# Task2.net
KiCad netlist of a schematic drawn in Altium Designer
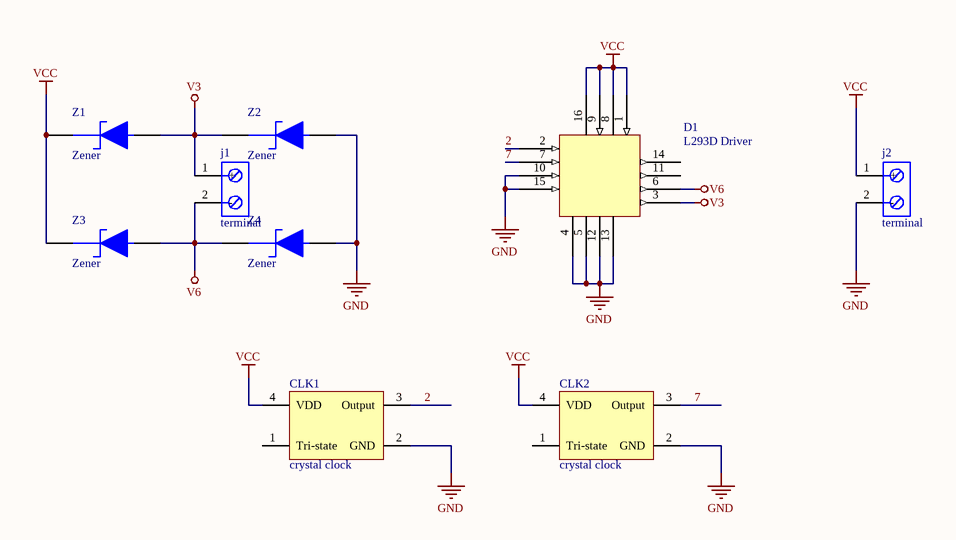
[diagram p0: Task2.SchDoc]

(export (version "E")
  (design (tool "Eeschema 10.0.6"))
  (components
    (comp (ref "CLK1")
      (value "crystal clock")
      (footprint "Crystal Oscillator")
      (description "Oscillator XO 0.032768MHz ±25ppm 15pF 60% 3.3V 4-Pin SMD T/R")
      (fields
        (field (name "MANUFACTURER") "Abracon")
        (field (name "MANUFACTURER PART NUMBER") "ASEK-32.768KHZ-L-R-T")
      )
      (libsource (lib "Integrated_Library1") (part "Crystal oscillator"))
    )
    (comp (ref "CLK2")
      (value "crystal clock")
      (footprint "Crystal Oscillator")
      (description "Oscillator XO 0.032768MHz ±25ppm 15pF 60% 3.3V 4-Pin SMD T/R")
      (fields
        (field (name "MANUFACTURER") "Abracon")
        (field (name "MANUFACTURER PART NUMBER") "ASEK-32.768KHZ-L-R-T")
      )
      (libsource (lib "Integrated_Library1") (part "Crystal oscillator"))
    )
    (comp (ref "D1")
      (value "L293D Driver")
      (footprint "Driver")
      (description "IC MTRDRV BIPLR 4.5-36V 16PWRDIP")
      (fields (field (name "PART NUMBER") "497-2936-5-ND"))
      (libsource (lib "Sch") (part "L293D Driver"))
    )
    (comp (ref "j1")
      (value "terminal")
      (footprint "TERMINAL")
      (description "Barrier Strip Terminal Block")
      (fields
        (field (name "MANUFACTURER") "Wurth Electronics")
        (field (name "MANUFACTURER PART NUMBER") "691137710002")
      )
      (libsource (lib "Integrated_Library1") (part "terminal"))
    )
    (comp (ref "j2")
      (value "terminal")
      (footprint "TERMINAL")
      (description "Barrier Strip Terminal Block")
      (fields
        (field (name "MANUFACTURER") "Wurth Electronics")
        (field (name "MANUFACTURER PART NUMBER") "691137710002")
      )
      (libsource (lib "Integrated_Library1") (part "terminal"))
    )
    (comp (ref "Z1")
      (value "Zener")
      (footprint "Zener")
      (description "TVS DIODE 5VWM SOD923")
      (fields (field (name "PART NUMBER") "ESD9B5.0ST5GOSDKR-ND"))
      (libsource (lib "Sch") (part "Zener"))
    )
    (comp (ref "Z2")
      (value "Zener")
      (footprint "Zener")
      (description "TVS DIODE 5VWM SOD923")
      (fields (field (name "PART NUMBER") "ESD9B5.0ST5GOSDKR-ND"))
      (libsource (lib "Sch") (part "Zener"))
    )
    (comp (ref "Z3")
      (value "Zener")
      (footprint "Zener")
      (description "TVS DIODE 5VWM SOD923")
      (fields (field (name "PART NUMBER") "ESD9B5.0ST5GOSDKR-ND"))
      (libsource (lib "Sch") (part "Zener"))
    )
    (comp (ref "Z4")
      (value "Zener")
      (footprint "Zener")
      (description "TVS DIODE 5VWM SOD923")
      (fields (field (name "PART NUMBER") "ESD9B5.0ST5GOSDKR-ND"))
      (libsource (lib "Sch") (part "Zener"))
    )
  )
  (nets
    (net (code "1") (name "/2") (class "Default")
      (node (ref "CLK1") (pin "3") (pinfunction "Output_3") (pintype "passive"))
      (node (ref "D1") (pin "2") (pintype "input"))
    )
    (net (code "2") (name "/7") (class "Default")
      (node (ref "CLK2") (pin "3") (pinfunction "Output_3") (pintype "passive"))
      (node (ref "D1") (pin "7") (pintype "input"))
    )
    (net (code "3") (name "GND") (class "Default")
      (node (ref "CLK1") (pin "2") (pinfunction "GND_2") (pintype "passive"))
      (node (ref "CLK2") (pin "2") (pinfunction "GND_2") (pintype "passive"))
      (node (ref "D1") (pin "10") (pintype "input"))
      (node (ref "D1") (pin "12") (pintype "power_in"))
      (node (ref "D1") (pin "13") (pintype "power_in"))
      (node (ref "D1") (pin "15") (pintype "input"))
      (node (ref "D1") (pin "4") (pintype "power_in"))
      (node (ref "D1") (pin "5") (pintype "power_in"))
      (node (ref "Z2") (pin "2") (pinfunction "2_2") (pintype "passive"))
      (node (ref "Z4") (pin "2") (pinfunction "2_2") (pintype "passive"))
      (node (ref "j2") (pin "2") (pinfunction "-_2") (pintype "passive"))
    )
    (net (code "4") (name "V3") (class "Default")
      (node (ref "D1") (pin "3") (pintype "output"))
      (node (ref "Z1") (pin "2") (pinfunction "2_2") (pintype "passive"))
      (node (ref "Z2") (pin "1") (pinfunction "1_1") (pintype "passive"))
      (node (ref "j1") (pin "1") (pinfunction "+_1") (pintype "passive"))
    )
    (net (code "5") (name "V6") (class "Default")
      (node (ref "D1") (pin "6") (pintype "output"))
      (node (ref "Z3") (pin "2") (pinfunction "2_2") (pintype "passive"))
      (node (ref "Z4") (pin "1") (pinfunction "1_1") (pintype "passive"))
      (node (ref "j1") (pin "2") (pinfunction "-_2") (pintype "passive"))
    )
    (net (code "6") (name "VCC") (class "Default")
      (node (ref "CLK1") (pin "4") (pinfunction "VDD_4") (pintype "passive"))
      (node (ref "CLK2") (pin "4") (pinfunction "VDD_4") (pintype "passive"))
      (node (ref "D1") (pin "1") (pintype "input"))
      (node (ref "D1") (pin "16") (pintype "power_in"))
      (node (ref "D1") (pin "8") (pintype "power_in"))
      (node (ref "D1") (pin "9") (pintype "input"))
      (node (ref "Z1") (pin "1") (pinfunction "1_1") (pintype "passive"))
      (node (ref "Z3") (pin "1") (pinfunction "1_1") (pintype "passive"))
      (node (ref "j2") (pin "1") (pinfunction "+_1") (pintype "passive"))
    )
    (net (code "7") (name "unconnected-(CLK1-Tri-state-Pad1)") (class "Default")
      (node (ref "CLK1") (pin "1") (pinfunction "Tri-state_1") (pintype "passive"))
    )
    (net (code "8") (name "unconnected-(CLK2-Tri-state-Pad1)") (class "Default")
      (node (ref "CLK2") (pin "1") (pinfunction "Tri-state_1") (pintype "passive"))
    )
    (net (code "9") (name "unconnected-(D1-Pad11)") (class "Default")
      (node (ref "D1") (pin "11") (pintype "output"))
    )
    (net (code "10") (name "unconnected-(D1-Pad14)") (class "Default")
      (node (ref "D1") (pin "14") (pintype "output"))
    )
  )
)
